# power.net
KiCad netlist of a schematic drawn in EAGLE
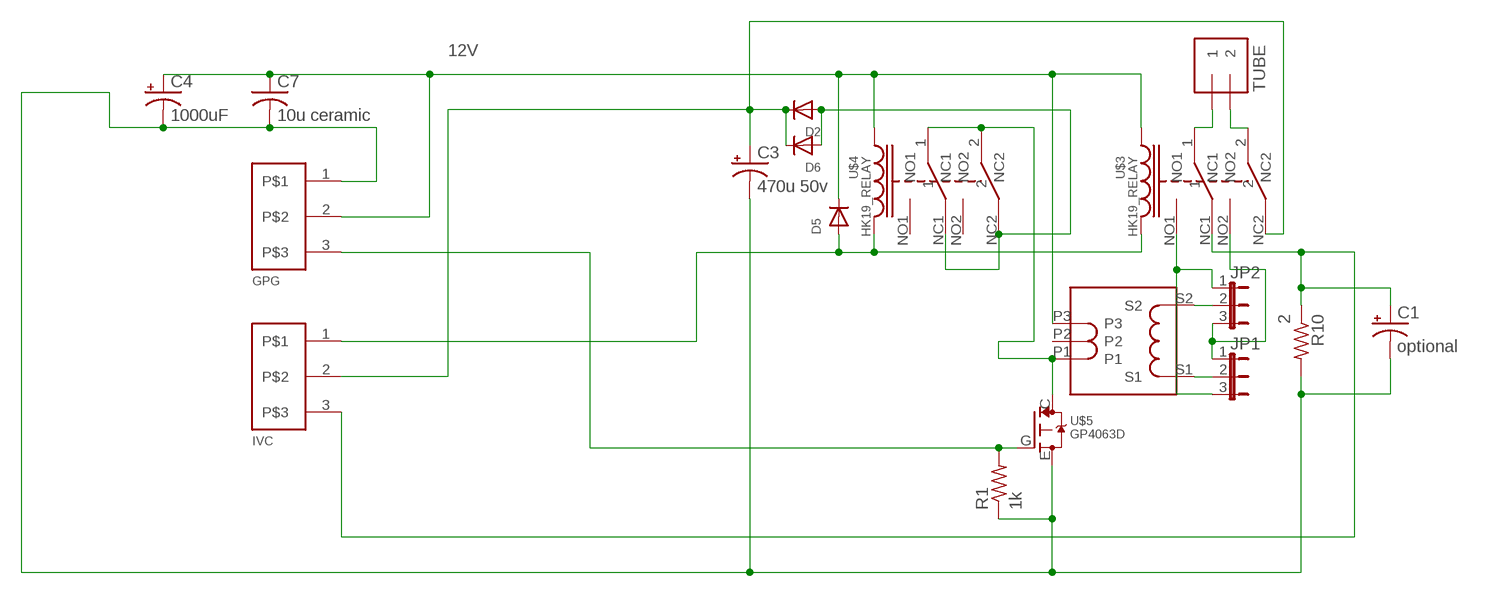
[diagram p0: schematic, sheet 1]

(export (version "E")
  (design (tool "Eeschema 10.0.6"))
  (components
    (comp (ref "C1")
      (value "optional")
      (footprint "eagle-import:E2,5-6")
      (libsource (lib "eagle-import") (part "CPOL-USE2.5-6"))
    )
    (comp (ref "C3")
      (value "470u 50v")
      (footprint "eagle-import:E5-10,5")
      (libsource (lib "eagle-import") (part "CPOL-USE5-10.5"))
    )
    (comp (ref "C4")
      (value "1000uF")
      (footprint "eagle-import:E5-10,5")
      (libsource (lib "eagle-import") (part "CPOL-USE5-10.5"))
    )
    (comp (ref "C7")
      (value "10u ceramic")
      (footprint "eagle-import:C050-045X075")
      (libsource (lib "eagle-import") (part "C-US050-045X075"))
    )
    (comp (ref "D2")
      (value "DIODEDO-1N4148")
      (footprint "eagle-import:DO-1N4148")
      (libsource (lib "eagle-import") (part "DIODEDO-1N4148"))
    )
    (comp (ref "D5")
      (value "DIODEDO-1N4148")
      (footprint "eagle-import:DO-1N4148")
      (libsource (lib "eagle-import") (part "DIODEDO-1N4148"))
    )
    (comp (ref "D6")
      (value "DIODEDO-1N4148")
      (footprint "eagle-import:DO-1N4148")
      (libsource (lib "eagle-import") (part "DIODEDO-1N4148"))
    )
    (comp (ref "GPG")
      (value "1X3_123")
      (footprint "eagle-import:1X3_123")
      (libsource (lib "eagle-import") (part "1X3_123"))
    )
    (comp (ref "IVC")
      (value "1X3_123")
      (footprint "eagle-import:1X3_123")
      (libsource (lib "eagle-import") (part "1X3_123"))
    )
    (comp (ref "JP1")
      (value "JP2E")
      (footprint "eagle-import:JP2")
      (libsource (lib "eagle-import") (part "JP2E"))
    )
    (comp (ref "JP2")
      (value "JP2E")
      (footprint "eagle-import:JP2")
      (libsource (lib "eagle-import") (part "JP2E"))
    )
    (comp (ref "R1")
      (value "1k")
      (footprint "eagle-import:0204V")
      (libsource (lib "eagle-import") (part "R-US_0204/2V"))
    )
    (comp (ref "R10")
      (value "2")
      (footprint "eagle-import:P0817V")
      (libsource (lib "eagle-import") (part "R-US_0817/7V"))
    )
    (comp (ref "TUBE")
      (value "1X2_1221")
      (footprint "eagle-import:1X2_21")
      (libsource (lib "eagle-import") (part "1X2_1221"))
    )
    (comp (ref "U$2")
      (value "TRANSFORMER_RAND_1")
      (footprint "eagle-import:TRANSFORMER_RAND_1")
      (libsource (lib "eagle-import") (part "TRANSFORMER_RAND_1"))
    )
    (comp (ref "U$3")
      (value "HK19_RELAY")
      (footprint "eagle-import:HK19RELAY")
      (libsource (lib "eagle-import") (part "HK19_RELAY"))
    )
    (comp (ref "U$4")
      (value "HK19_RELAY")
      (footprint "eagle-import:HK19RELAY")
      (libsource (lib "eagle-import") (part "HK19_RELAY"))
    )
    (comp (ref "U$5")
      (value "GP4063D")
      (footprint "eagle-import:TO247")
      (libsource (lib "eagle-import") (part "GP4063D"))
    )
  )
  (nets
    (net (code "1") (name "/12V") (class "Default")
      (node (ref "C4") (pin "+") (pinfunction "+_+") (pintype "passive"))
      (node (ref "C7") (pin "1") (pinfunction "1_1") (pintype "passive"))
      (node (ref "D5") (pin "C") (pinfunction "C_C") (pintype "passive"))
      (node (ref "GPG") (pin "2") (pinfunction "P$2_2") (pintype "bidirectional"))
      (node (ref "U$2") (pin "P3") (pinfunction "P3_P3") (pintype "bidirectional"))
      (node (ref "U$3") (pin "C1") (pinfunction "C1_C1") (pintype "bidirectional"))
      (node (ref "U$4") (pin "C1") (pinfunction "C1_C1") (pintype "bidirectional"))
    )
    (net (code "2") (name "Net-(D2-PadA)") (class "Default")
      (node (ref "D2") (pin "A") (pinfunction "A_A") (pintype "passive"))
      (node (ref "D6") (pin "A") (pinfunction "A_A") (pintype "passive"))
      (node (ref "U$4") (pin "NC1") (pinfunction "NC1_NC1") (pintype "bidirectional"))
      (node (ref "U$4") (pin "NC2") (pinfunction "NC2_NC2") (pintype "bidirectional"))
    )
    (net (code "3") (name "Net-(GPG-P$1)") (class "Default")
      (node (ref "C1") (pin "-") (pinfunction "-_-") (pintype "passive"))
      (node (ref "C3") (pin "-") (pinfunction "-_-") (pintype "passive"))
      (node (ref "C4") (pin "-") (pinfunction "-_-") (pintype "passive"))
      (node (ref "C7") (pin "2") (pinfunction "2_2") (pintype "passive"))
      (node (ref "GPG") (pin "1") (pinfunction "P$1_1") (pintype "bidirectional"))
      (node (ref "R1") (pin "1") (pinfunction "1_1") (pintype "passive"))
      (node (ref "R10") (pin "2") (pinfunction "2_2") (pintype "passive"))
      (node (ref "U$5") (pin "E") (pinfunction "E_E") (pintype "bidirectional"))
    )
    (net (code "4") (name "Net-(GPG-P$3)") (class "Default")
      (node (ref "GPG") (pin "3") (pinfunction "P$3_3") (pintype "bidirectional"))
      (node (ref "R1") (pin "2") (pinfunction "2_2") (pintype "passive"))
      (node (ref "U$5") (pin "G") (pinfunction "G_G") (pintype "bidirectional"))
    )
    (net (code "5") (name "Net-(IVC-P$1)") (class "Default")
      (node (ref "D5") (pin "A") (pinfunction "A_A") (pintype "passive"))
      (node (ref "IVC") (pin "1") (pinfunction "P$1_1") (pintype "bidirectional"))
      (node (ref "U$3") (pin "C2") (pinfunction "C2_C2") (pintype "bidirectional"))
      (node (ref "U$4") (pin "C2") (pinfunction "C2_C2") (pintype "bidirectional"))
    )
    (net (code "6") (name "Net-(IVC-P$2)") (class "Default")
      (node (ref "C3") (pin "+") (pinfunction "+_+") (pintype "passive"))
      (node (ref "D2") (pin "C") (pinfunction "C_C") (pintype "passive"))
      (node (ref "D6") (pin "C") (pinfunction "C_C") (pintype "passive"))
      (node (ref "IVC") (pin "2") (pinfunction "P$2_2") (pintype "bidirectional"))
      (node (ref "U$3") (pin "NC2") (pinfunction "NC2_NC2") (pintype "bidirectional"))
    )
    (net (code "7") (name "Net-(IVC-P$3)") (class "Default")
      (node (ref "C1") (pin "+") (pinfunction "+_+") (pintype "passive"))
      (node (ref "IVC") (pin "3") (pinfunction "P$3_3") (pintype "bidirectional"))
      (node (ref "R10") (pin "1") (pinfunction "1_1") (pintype "passive"))
      (node (ref "U$3") (pin "NC1") (pinfunction "NC1_NC1") (pintype "bidirectional"))
    )
    (net (code "8") (name "Net-(JP1-Pad1)") (class "Default")
      (node (ref "JP1") (pin "1") (pinfunction "1_1") (pintype "passive"))
      (node (ref "JP2") (pin "3") (pinfunction "3_3") (pintype "passive"))
      (node (ref "U$3") (pin "NO2") (pinfunction "NO2_NO2") (pintype "bidirectional"))
    )
    (net (code "9") (name "Net-(JP1-Pad2)") (class "Default")
      (node (ref "JP1") (pin "2") (pinfunction "2_2") (pintype "passive"))
      (node (ref "U$2") (pin "S1") (pinfunction "S1_S1") (pintype "bidirectional"))
    )
    (net (code "10") (name "Net-(JP1-Pad3)") (class "Default")
      (node (ref "JP1") (pin "3") (pinfunction "3_3") (pintype "passive"))
      (node (ref "JP2") (pin "1") (pinfunction "1_1") (pintype "passive"))
      (node (ref "U$3") (pin "NO1") (pinfunction "NO1_NO1") (pintype "bidirectional"))
    )
    (net (code "11") (name "Net-(JP2-Pad2)") (class "Default")
      (node (ref "JP2") (pin "2") (pinfunction "2_2") (pintype "passive"))
      (node (ref "U$2") (pin "S2") (pinfunction "S2_S2") (pintype "bidirectional"))
    )
    (net (code "12") (name "Net-(TUBE-Pad1)") (class "Default")
      (node (ref "TUBE") (pin "1") (pinfunction "1_1") (pintype "passive"))
      (node (ref "U$3") (pin "1") (pinfunction "1_1") (pintype "bidirectional"))
    )
    (net (code "13") (name "Net-(TUBE-Pad2)") (class "Default")
      (node (ref "TUBE") (pin "2") (pinfunction "2_2") (pintype "passive"))
      (node (ref "U$3") (pin "2") (pinfunction "2_2") (pintype "bidirectional"))
    )
    (net (code "14") (name "Net-(U$2-PadP1)") (class "Default")
      (node (ref "U$2") (pin "P1") (pinfunction "P1_P1") (pintype "bidirectional"))
      (node (ref "U$4") (pin "1") (pinfunction "1_1") (pintype "bidirectional"))
      (node (ref "U$4") (pin "2") (pinfunction "2_2") (pintype "bidirectional"))
      (node (ref "U$5") (pin "C") (pinfunction "C_C") (pintype "bidirectional"))
    )
    (net (code "15") (name "unconnected-(U$2-PadP2)") (class "Default")
      (node (ref "U$2") (pin "P2") (pinfunction "P2_P2") (pintype "bidirectional"))
    )
    (net (code "16") (name "unconnected-(U$4-PadNO1)") (class "Default")
      (node (ref "U$4") (pin "NO1") (pinfunction "NO1_NO1") (pintype "bidirectional"))
    )
    (net (code "17") (name "unconnected-(U$4-PadNO2)") (class "Default")
      (node (ref "U$4") (pin "NO2") (pinfunction "NO2_NO2") (pintype "bidirectional"))
    )
  )
)
